# ORD_POWER.net
KiCad netlist of a schematic drawn in Altium Designer
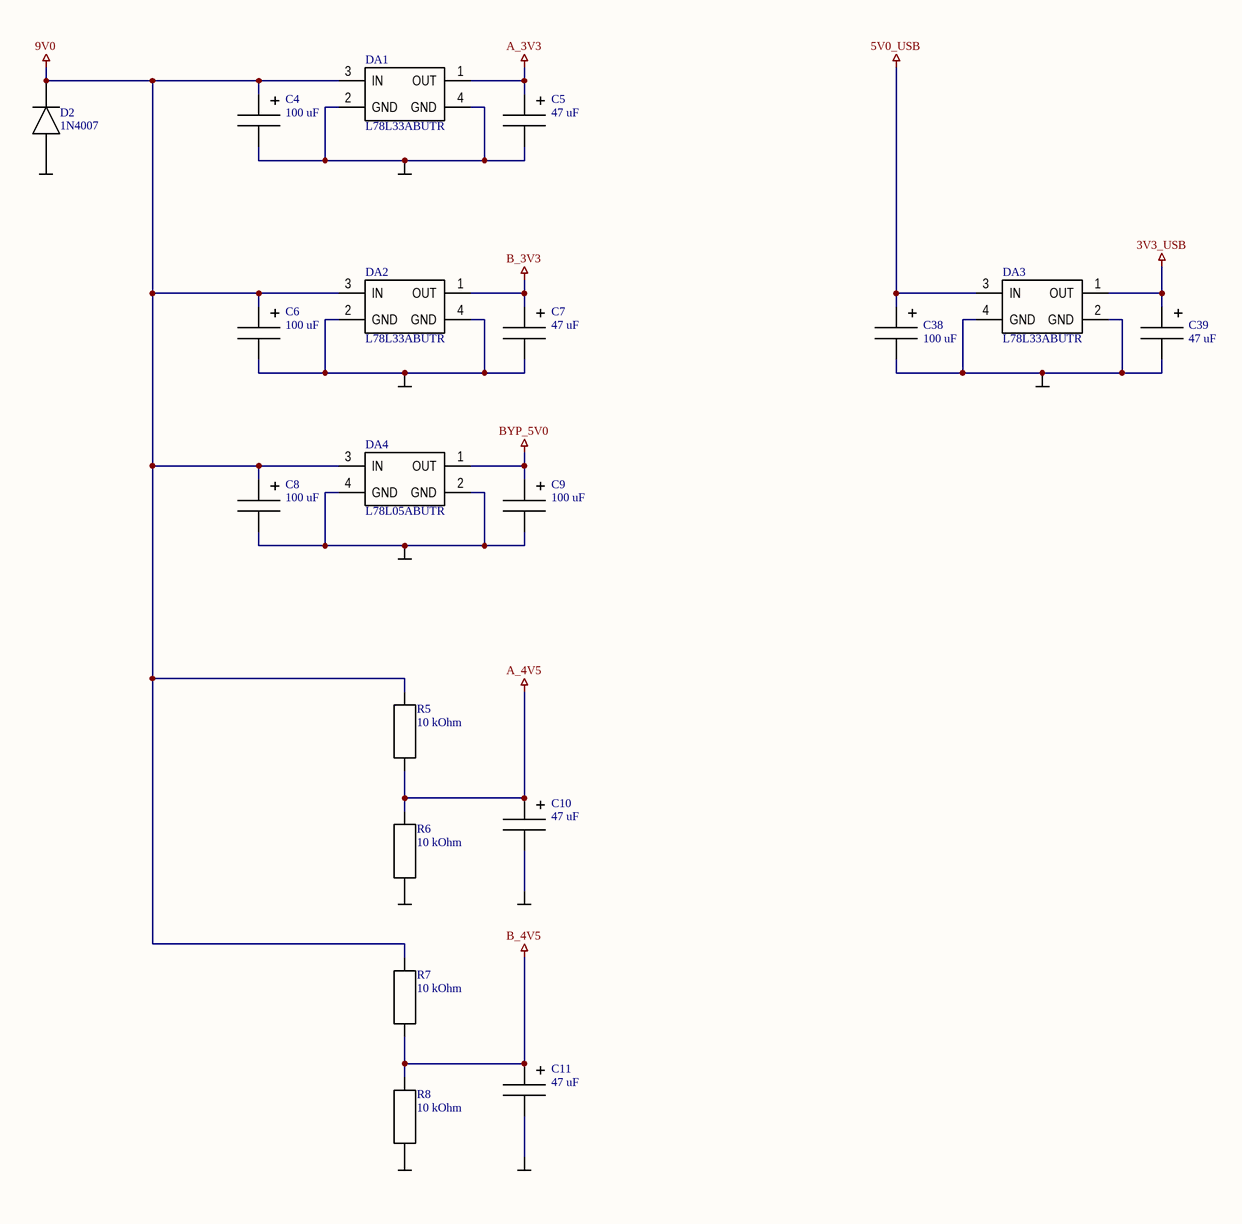
[diagram p0: ORD_POWER.SchDoc]

(export (version "E")
  (design (tool "Eeschema 10.0.6"))
  (components
    (comp (ref "C4")
      (value "100 uF")
      (footprint "C7343_CASE-D")
      (libsource (lib "Gost_passive_lib") (part "Capacitor_Pol"))
    )
    (comp (ref "C5")
      (value "47 uF")
      (footprint "C3528_CASE-B")
      (libsource (lib "Gost_passive_lib") (part "Capacitor_Pol"))
    )
    (comp (ref "C6")
      (value "100 uF")
      (footprint "C7343_CASE-D")
      (libsource (lib "Gost_passive_lib") (part "Capacitor_Pol"))
    )
    (comp (ref "C7")
      (value "47 uF")
      (footprint "C3528_CASE-B")
      (libsource (lib "Gost_passive_lib") (part "Capacitor_Pol"))
    )
    (comp (ref "C8")
      (value "100 uF")
      (footprint "C7343_CASE-D")
      (libsource (lib "Gost_passive_lib") (part "Capacitor_Pol"))
    )
    (comp (ref "C9")
      (value "100 uF")
      (footprint "C3528_CASE-B")
      (libsource (lib "Gost_passive_lib") (part "Capacitor_Pol"))
    )
    (comp (ref "C10")
      (value "47 uF")
      (footprint "C3528_CASE-B")
      (libsource (lib "Gost_passive_lib") (part "Capacitor_Pol"))
    )
    (comp (ref "C11")
      (value "47 uF")
      (footprint "C3528_CASE-B")
      (libsource (lib "Gost_passive_lib") (part "Capacitor_Pol"))
    )
    (comp (ref "C38")
      (value "100 uF")
      (footprint "C7343_CASE-D")
      (libsource (lib "Gost_passive_lib") (part "Capacitor_Pol"))
    )
    (comp (ref "C39")
      (value "47 uF")
      (footprint "C3528_CASE-B")
      (libsource (lib "Gost_passive_lib") (part "Capacitor_Pol"))
    )
    (comp (ref "D2")
      (value "1N4007")
      (footprint "DO-41")
      (libsource (lib "Gost_passive_lib") (part "1N4007"))
    )
    (comp (ref "DA1")
      (value "L78L33ABUTR")
      (footprint "SOT-89")
      (fields
        (field (name "MANUFACTURER_PART_NUMBER") "NJM78L05UA-TE1")
        (field (name "RS PART NUMBER") "7139502P")
      )
      (libsource (lib "Gost_power_libs") (part "L78L33ABUTR"))
    )
    (comp (ref "DA2")
      (value "L78L33ABUTR")
      (footprint "SOT-89")
      (fields
        (field (name "MANUFACTURER_PART_NUMBER") "NJM78L05UA-TE1")
        (field (name "RS PART NUMBER") "7139502P")
      )
      (libsource (lib "Gost_power_libs") (part "L78L33ABUTR"))
    )
    (comp (ref "DA3")
      (value "L78L33ABUTR")
      (footprint "SOT-89")
      (fields
        (field (name "MANUFACTURER_PART_NUMBER") "NJM78L05UA-TE1")
        (field (name "RS PART NUMBER") "7139502P")
      )
      (libsource (lib "") (part "L78L33ABUTR_1"))
    )
    (comp (ref "DA4")
      (value "L78L05ABUTR")
      (footprint "SOT-89")
      (fields
        (field (name "MANUFACTURER_PART_NUMBER") "NJM78L05UA-TE1")
        (field (name "RS PART NUMBER") "7139502P")
      )
      (libsource (lib "Gost_power_libs") (part "L78L05ABUTR"))
    )
    (comp (ref "R5")
      (value "10 kOhm")
      (footprint "R0805[2012]")
      (libsource (lib "Gost_passive_lib") (part "Resistor"))
    )
    (comp (ref "R6")
      (value "10 kOhm")
      (footprint "R0805[2012]")
      (libsource (lib "Gost_passive_lib") (part "Resistor"))
    )
    (comp (ref "R7")
      (value "10 kOhm")
      (footprint "R0805[2012]")
      (libsource (lib "Gost_passive_lib") (part "Resistor"))
    )
    (comp (ref "R8")
      (value "10 kOhm")
      (footprint "R0805[2012]")
      (libsource (lib "Gost_passive_lib") (part "Resistor"))
    )
  )
  (nets
    (net (code "1") (name "3V3_USB") (class "Default")
      (node (ref "C39") (pin "1") (pinfunction "1_1") (pintype "passive"))
      (node (ref "DA3") (pin "1") (pinfunction "OUT_1") (pintype "passive"))
    )
    (net (code "2") (name "5V0_USB") (class "Default")
      (node (ref "C38") (pin "1") (pinfunction "1_1") (pintype "passive"))
      (node (ref "DA3") (pin "3") (pinfunction "IN_3") (pintype "passive"))
    )
    (net (code "3") (name "9V0") (class "Default")
      (node (ref "C4") (pin "1") (pinfunction "1_1") (pintype "passive"))
      (node (ref "C6") (pin "1") (pinfunction "1_1") (pintype "passive"))
      (node (ref "C8") (pin "1") (pinfunction "1_1") (pintype "passive"))
      (node (ref "D2") (pin "1") (pinfunction "K_1") (pintype "passive"))
      (node (ref "DA1") (pin "3") (pinfunction "IN_3") (pintype "passive"))
      (node (ref "DA2") (pin "3") (pinfunction "IN_3") (pintype "passive"))
      (node (ref "DA4") (pin "3") (pinfunction "IN_3") (pintype "passive"))
      (node (ref "R5") (pin "2") (pinfunction "2_2") (pintype "passive"))
      (node (ref "R7") (pin "2") (pinfunction "2_2") (pintype "passive"))
    )
    (net (code "4") (name "A_3V3") (class "Default")
      (node (ref "C5") (pin "1") (pinfunction "1_1") (pintype "passive"))
      (node (ref "DA1") (pin "1") (pinfunction "OUT_1") (pintype "passive"))
    )
    (net (code "5") (name "A_4V5") (class "Default")
      (node (ref "C10") (pin "1") (pinfunction "1_1") (pintype "passive"))
      (node (ref "R5") (pin "1") (pinfunction "1_1") (pintype "passive"))
      (node (ref "R6") (pin "2") (pinfunction "2_2") (pintype "passive"))
    )
    (net (code "6") (name "BYP_5V0") (class "Default")
      (node (ref "C9") (pin "1") (pinfunction "1_1") (pintype "passive"))
      (node (ref "DA4") (pin "1") (pinfunction "OUT_1") (pintype "passive"))
    )
    (net (code "7") (name "B_3V3") (class "Default")
      (node (ref "C7") (pin "1") (pinfunction "1_1") (pintype "passive"))
      (node (ref "DA2") (pin "1") (pinfunction "OUT_1") (pintype "passive"))
    )
    (net (code "8") (name "B_4V5") (class "Default")
      (node (ref "C11") (pin "1") (pinfunction "1_1") (pintype "passive"))
      (node (ref "R7") (pin "1") (pinfunction "1_1") (pintype "passive"))
      (node (ref "R8") (pin "2") (pinfunction "2_2") (pintype "passive"))
    )
    (net (code "9") (name "GND") (class "Default")
      (node (ref "C10") (pin "2") (pinfunction "2_2") (pintype "passive"))
      (node (ref "C11") (pin "2") (pinfunction "2_2") (pintype "passive"))
      (node (ref "C38") (pin "2") (pinfunction "2_2") (pintype "passive"))
      (node (ref "C39") (pin "2") (pinfunction "2_2") (pintype "passive"))
      (node (ref "C4") (pin "2") (pinfunction "2_2") (pintype "passive"))
      (node (ref "C5") (pin "2") (pinfunction "2_2") (pintype "passive"))
      (node (ref "C6") (pin "2") (pinfunction "2_2") (pintype "passive"))
      (node (ref "C7") (pin "2") (pinfunction "2_2") (pintype "passive"))
      (node (ref "C8") (pin "2") (pinfunction "2_2") (pintype "passive"))
      (node (ref "C9") (pin "2") (pinfunction "2_2") (pintype "passive"))
      (node (ref "D2") (pin "2") (pinfunction "A_2") (pintype "passive"))
      (node (ref "DA1") (pin "2") (pinfunction "GND_2") (pintype "passive"))
      (node (ref "DA1") (pin "4") (pinfunction "GND_4") (pintype "passive"))
      (node (ref "DA2") (pin "2") (pinfunction "GND_2") (pintype "passive"))
      (node (ref "DA2") (pin "4") (pinfunction "GND_4") (pintype "passive"))
      (node (ref "DA3") (pin "2") (pinfunction "GND_2") (pintype "passive"))
      (node (ref "DA3") (pin "4") (pinfunction "GND_4") (pintype "passive"))
      (node (ref "DA4") (pin "2") (pinfunction "GND_2") (pintype "passive"))
      (node (ref "DA4") (pin "4") (pinfunction "GND_4") (pintype "passive"))
      (node (ref "R6") (pin "1") (pinfunction "1_1") (pintype "passive"))
      (node (ref "R8") (pin "1") (pinfunction "1_1") (pintype "passive"))
    )
  )
)
